# Microcontroller.net
KiCad netlist of a schematic drawn in Altium Designer
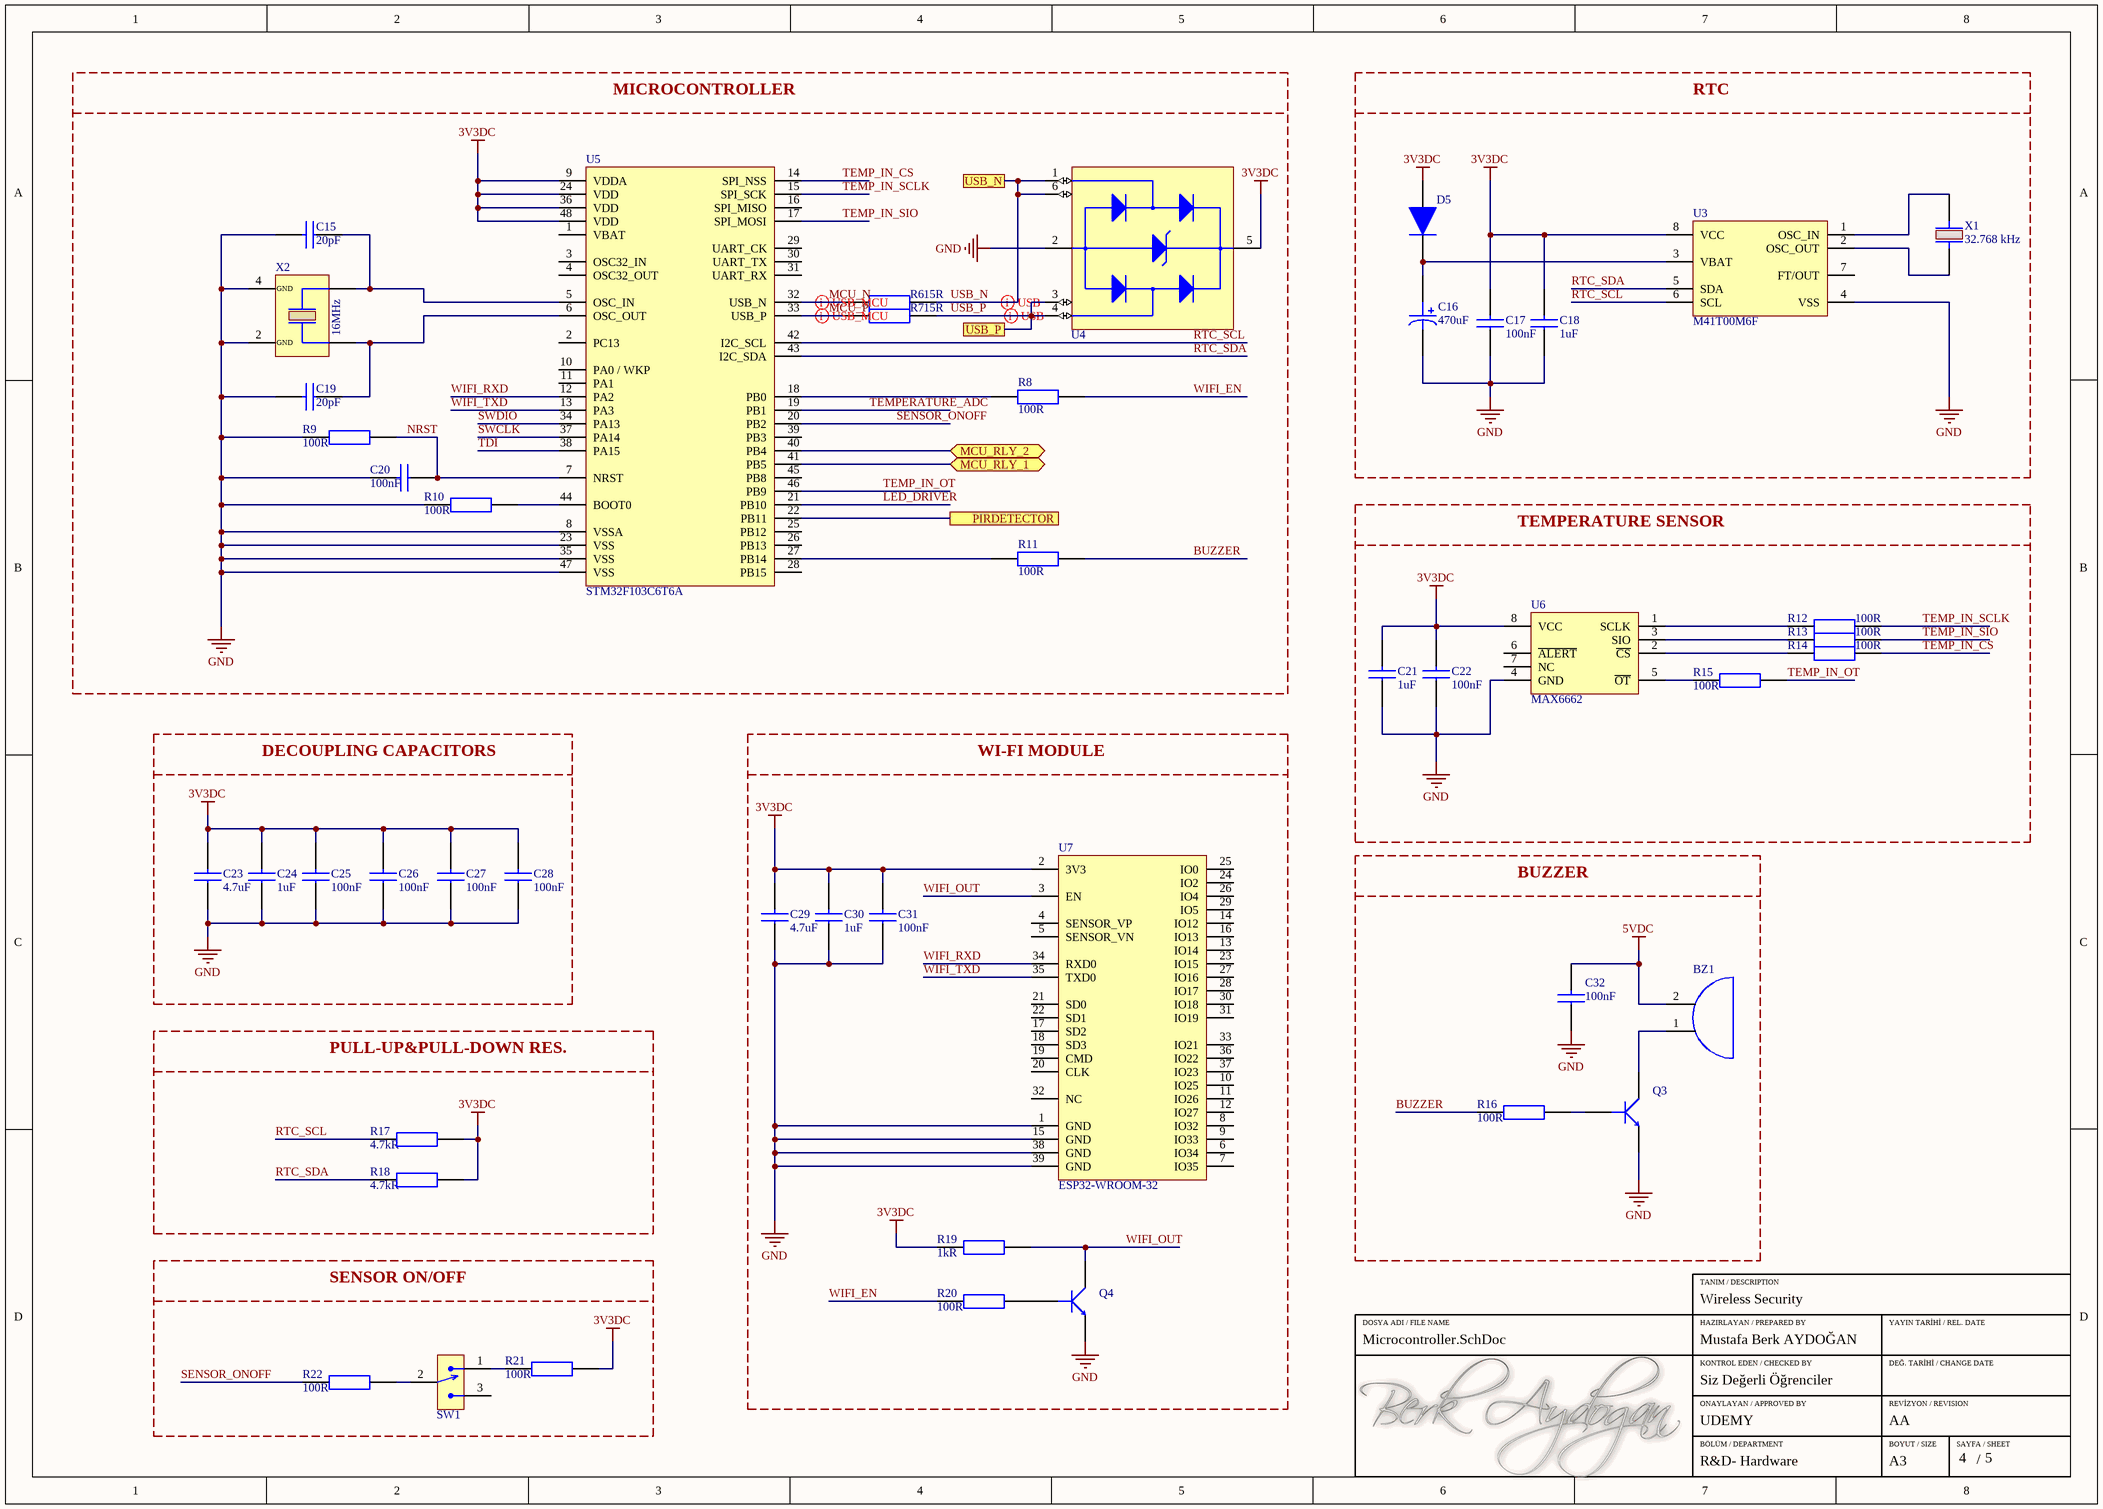
[diagram p0: Microcontroller.SchDoc]

(export (version "E")
  (design (tool "Eeschema 10.0.6"))
  (components
    (comp (ref "BZ1")
      (value "CMI-9605IC-0580T")
      (footprint "CMI-9605IC")
      (description "Buzzers Indicator, Internally Driven Magnetic 5V 30mA 2.7kHz 80dB @ 5V, 10cm Through Hole PC Pins")
      (fields (field (name "MANUFACTURER") "CUI Devices") (field (name "DESIGNED BY") "BERK"))
      (libsource (lib "UDEMY_Library") (part "CMI-9605IC-0580T"))
    )
    (comp (ref "C15")
      (value "CL10C200JB8NNNC")
      (footprint "CAP_0603")
      (description "CAP CER 20pF %5 0603 SMD")
      (fields
        (field (name "MANUFACTURER") "Samsung")
        (field (name "TOLERANCE") "5%")
        (field (name "CAPACITANCE") "20pF")
        (field (name "DESIGNED BY") "BERK")
      )
      (libsource (lib "UDEMY_Library") (part "CAP CER 20pF 0603"))
    )
    (comp (ref "C16")
      (value "ESH477M050AH4AA")
      (footprint "CAP_RADIAL_D10_P5")
      (description "CAP ALU ELEC 470uF 50V RADIAL")
      (fields
        (field (name "MANUFACTURER") "KEMET")
        (field (name "TOLERANCE") "20%")
        (field (name "CAPACITANCE") "470uF")
        (field (name "DESIGNED BY") "BERK")
      )
      (libsource (lib "UDEMY_Library") (part "CAP ALU ELEC 470uF 50V"))
    )
    (comp (ref "C17")
      (value "CL21B104KBCNNNC")
      (footprint "CAP_0805")
      (description "CAP CER 100nF %10 0805")
      (fields
        (field (name "MANUFACTURER") "Samsung")
        (field (name "TOLERANCE") "10%")
        (field (name "CAPACITANCE") "100nF")
        (field (name "DESIGNED BY") "BERK")
      )
      (libsource (lib "UDEMY_Library") (part "CAP CER 100nF 0805"))
    )
    (comp (ref "C18")
      (value "CL21B105KBFNNNE")
      (footprint "CAP_0805")
      (description "CAP CER 1uF %10 0805")
      (fields
        (field (name "MANUFACTURER") "Samsung")
        (field (name "TOLERANCE") "10%")
        (field (name "CAPACITANCE") "1uF")
        (field (name "DESIGNED BY") "BERK")
      )
      (libsource (lib "UDEMY_Library") (part "CAP CER 1uF 0805"))
    )
    (comp (ref "C19")
      (value "CL10C200JB8NNNC")
      (footprint "CAP_0603")
      (description "CAP CER 20pF %5 0603 SMD")
      (fields
        (field (name "MANUFACTURER") "Samsung")
        (field (name "TOLERANCE") "5%")
        (field (name "CAPACITANCE") "20pF")
        (field (name "DESIGNED BY") "BERK")
      )
      (libsource (lib "UDEMY_Library") (part "CAP CER 20pF 0603"))
    )
    (comp (ref "C20")
      (value "C0603C104K5RACTU")
      (footprint "CAP_0603")
      (description "CAP CER 100nF %10 0603 SMD")
      (fields
        (field (name "MANUFACTURER") "KEMET")
        (field (name "TOLERANCE") "10%")
        (field (name "CAPACITANCE") "100nF")
        (field (name "DESIGNED BY") "BERK")
      )
      (libsource (lib "UDEMY_Library") (part "CAP CER 100nF 0603"))
    )
    (comp (ref "C21")
      (value "CL21B105KBFNNNE")
      (footprint "CAP_0805")
      (description "CAP CER 1uF %10 0805")
      (fields
        (field (name "MANUFACTURER") "Samsung")
        (field (name "TOLERANCE") "10%")
        (field (name "CAPACITANCE") "1uF")
        (field (name "DESIGNED BY") "BERK")
      )
      (libsource (lib "UDEMY_Library") (part "CAP CER 1uF 0805"))
    )
    (comp (ref "C22")
      (value "CL21B104KBCNNNC")
      (footprint "CAP_0805")
      (description "CAP CER 100nF %10 0805")
      (fields
        (field (name "MANUFACTURER") "Samsung")
        (field (name "TOLERANCE") "10%")
        (field (name "CAPACITANCE") "100nF")
        (field (name "DESIGNED BY") "BERK")
      )
      (libsource (lib "UDEMY_Library") (part "CAP CER 100nF 0805"))
    )
    (comp (ref "C23")
      (value "CL21A475KAQNNNE")
      (footprint "CAP_0805")
      (description "CAP CER 4.7uF %10 0805")
      (fields
        (field (name "MANUFACTURER") "Samsung")
        (field (name "TOLERANCE") "10%")
        (field (name "CAPACITANCE") "4.7uF")
        (field (name "DESIGNED BY") "BERK")
      )
      (libsource (lib "UDEMY_Library") (part "CAP CER 4.7uF 0805"))
    )
    (comp (ref "C24")
      (value "CL21B105KBFNNNE")
      (footprint "CAP_0805")
      (description "CAP CER 1uF %10 0805")
      (fields
        (field (name "MANUFACTURER") "Samsung")
        (field (name "TOLERANCE") "10%")
        (field (name "CAPACITANCE") "1uF")
        (field (name "DESIGNED BY") "BERK")
      )
      (libsource (lib "UDEMY_Library") (part "CAP CER 1uF 0805"))
    )
    (comp (ref "C25")
      (value "C0603C104K5RACTU")
      (footprint "CAP_0603")
      (description "CAP CER 100nF %10 0603 SMD")
      (fields
        (field (name "MANUFACTURER") "KEMET")
        (field (name "TOLERANCE") "10%")
        (field (name "CAPACITANCE") "100nF")
        (field (name "DESIGNED BY") "BERK")
      )
      (libsource (lib "UDEMY_Library") (part "CAP CER 100nF 0603"))
    )
    (comp (ref "C26")
      (value "C0603C104K5RACTU")
      (footprint "CAP_0603")
      (description "CAP CER 100nF %10 0603 SMD")
      (fields
        (field (name "MANUFACTURER") "KEMET")
        (field (name "TOLERANCE") "10%")
        (field (name "CAPACITANCE") "100nF")
        (field (name "DESIGNED BY") "BERK")
      )
      (libsource (lib "UDEMY_Library") (part "CAP CER 100nF 0603"))
    )
    (comp (ref "C27")
      (value "C0603C104K5RACTU")
      (footprint "CAP_0603")
      (description "CAP CER 100nF %10 0603 SMD")
      (fields
        (field (name "MANUFACTURER") "KEMET")
        (field (name "TOLERANCE") "10%")
        (field (name "CAPACITANCE") "100nF")
        (field (name "DESIGNED BY") "BERK")
      )
      (libsource (lib "UDEMY_Library") (part "CAP CER 100nF 0603"))
    )
    (comp (ref "C28")
      (value "C0603C104K5RACTU")
      (footprint "CAP_0603")
      (description "CAP CER 100nF %10 0603 SMD")
      (fields
        (field (name "MANUFACTURER") "KEMET")
        (field (name "TOLERANCE") "10%")
        (field (name "CAPACITANCE") "100nF")
        (field (name "DESIGNED BY") "BERK")
      )
      (libsource (lib "UDEMY_Library") (part "CAP CER 100nF 0603"))
    )
    (comp (ref "C29")
      (value "CL21A475KAQNNNE")
      (footprint "CAP_0805")
      (description "CAP CER 4.7uF %10 0805")
      (fields
        (field (name "MANUFACTURER") "Samsung")
        (field (name "TOLERANCE") "10%")
        (field (name "CAPACITANCE") "4.7uF")
        (field (name "DESIGNED BY") "BERK")
      )
      (libsource (lib "UDEMY_Library") (part "CAP CER 4.7uF 0805"))
    )
    (comp (ref "C30")
      (value "CL21B105KBFNNNE")
      (footprint "CAP_0805")
      (description "CAP CER 1uF %10 0805")
      (fields
        (field (name "MANUFACTURER") "Samsung")
        (field (name "TOLERANCE") "10%")
        (field (name "CAPACITANCE") "1uF")
        (field (name "DESIGNED BY") "BERK")
      )
      (libsource (lib "UDEMY_Library") (part "CAP CER 1uF 0805"))
    )
    (comp (ref "C31")
      (value "CL21B104KBCNNNC")
      (footprint "CAP_0805")
      (description "CAP CER 100nF %10 0805")
      (fields
        (field (name "MANUFACTURER") "Samsung")
        (field (name "TOLERANCE") "10%")
        (field (name "CAPACITANCE") "100nF")
        (field (name "DESIGNED BY") "BERK")
      )
      (libsource (lib "UDEMY_Library") (part "CAP CER 100nF 0805"))
    )
    (comp (ref "C32")
      (value "CL21B104KBCNNNC")
      (footprint "CAP_0805")
      (description "CAP CER 100nF %10 0805")
      (fields
        (field (name "MANUFACTURER") "Samsung")
        (field (name "TOLERANCE") "10%")
        (field (name "CAPACITANCE") "100nF")
        (field (name "DESIGNED BY") "BERK")
      )
      (libsource (lib "UDEMY_Library") (part "CAP CER 100nF 0805"))
    )
    (comp (ref "D5")
      (value "1N4148WS")
      (footprint "SOD323F")
      (description "Diode, Single, 75 V, 150 mA, 1 V, 4 ns")
      (fields
        (field (name "MANUFACTURER") "ON Semiconductor / Fairchild")
        (field (name "DESIGNED BY") "BERK")
      )
      (libsource (lib "UDEMY_Library") (part "1N4148WS"))
    )
    (comp (ref "Q3")
      (value "MMBT3904-7-F")
      (footprint "SOT-23F")
      (description "Transistor General Purpose BJT NPN 40 Volt 0.2A Automotive 3-Pin SOT-23")
      (fields (field (name "MANUFACTURER") "Diodes Zetex") (field (name "DESIGNED BY") "BERK"))
      (libsource (lib "UDEMY_Library") (part "MMBT3904-7-F"))
    )
    (comp (ref "Q4")
      (value "MMBT3904-7-F")
      (footprint "SOT-23F")
      (description "Transistor General Purpose BJT NPN 40 Volt 0.2A Automotive 3-Pin SOT-23")
      (fields (field (name "MANUFACTURER") "Diodes Zetex") (field (name "DESIGNED BY") "BERK"))
      (libsource (lib "UDEMY_Library") (part "MMBT3904-7-F"))
    )
    (comp (ref "R6")
      (value "RC0603JR-0715RL")
      (footprint "RES_0603")
      (description "RES 15 %5 OHM 0603 SMD")
      (fields
        (field (name "MANUFACTURER") "Yageo")
        (field (name "TOLERANCE") "5%")
        (field (name "RESISTANCE") "15R")
        (field (name "DESIGNED BY") "BERK")
      )
      (libsource (lib "UDEMY_Library") (part "RES 15 OHM 0603"))
    )
    (comp (ref "R7")
      (value "RC0603JR-0715RL")
      (footprint "RES_0603")
      (description "RES 15 %5 OHM 0603 SMD")
      (fields
        (field (name "MANUFACTURER") "Yageo")
        (field (name "TOLERANCE") "5%")
        (field (name "RESISTANCE") "15R")
        (field (name "DESIGNED BY") "BERK")
      )
      (libsource (lib "UDEMY_Library") (part "RES 15 OHM 0603"))
    )
    (comp (ref "R8")
      (value "RC0603JR-07100RL")
      (footprint "RES_0603")
      (description "RES 100 %5 OHM 0603 SMD")
      (fields
        (field (name "MANUFACTURER") "Yageo")
        (field (name "TOLERANCE") "5%")
        (field (name "RESISTANCE") "100R")
        (field (name "DESIGNED BY") "BERK")
      )
      (libsource (lib "") (part "RES 100 OHM 0603_1"))
    )
    (comp (ref "R9")
      (value "RC0603JR-07100RL")
      (footprint "RES_0603")
      (description "RES 100 %5 OHM 0603 SMD")
      (fields
        (field (name "MANUFACTURER") "Yageo")
        (field (name "TOLERANCE") "5%")
        (field (name "RESISTANCE") "100R")
        (field (name "DESIGNED BY") "BERK")
      )
      (libsource (lib "") (part "RES 100 OHM 0603_1"))
    )
    (comp (ref "R10")
      (value "RC0603JR-07100RL")
      (footprint "RES_0603")
      (description "RES 100 %5 OHM 0603 SMD")
      (fields
        (field (name "MANUFACTURER") "Yageo")
        (field (name "TOLERANCE") "5%")
        (field (name "RESISTANCE") "100R")
        (field (name "DESIGNED BY") "BERK")
      )
      (libsource (lib "") (part "RES 100 OHM 0603_1"))
    )
    (comp (ref "R11")
      (value "RC0603JR-07100RL")
      (footprint "RES_0603")
      (description "RES 100 %5 OHM 0603 SMD")
      (fields
        (field (name "MANUFACTURER") "Yageo")
        (field (name "TOLERANCE") "5%")
        (field (name "RESISTANCE") "100R")
        (field (name "DESIGNED BY") "BERK")
      )
      (libsource (lib "") (part "RES 100 OHM 0603_1"))
    )
    (comp (ref "R12")
      (value "RC0603JR-07100RL")
      (footprint "RES_0603")
      (description "RES 100 %5 OHM 0603 SMD")
      (fields
        (field (name "MANUFACTURER") "Yageo")
        (field (name "TOLERANCE") "5%")
        (field (name "RESISTANCE") "100R")
        (field (name "DESIGNED BY") "BERK")
      )
      (libsource (lib "") (part "RES 100 OHM 0603_1"))
    )
    (comp (ref "R13")
      (value "RC0603JR-07100RL")
      (footprint "RES_0603")
      (description "RES 100 %5 OHM 0603 SMD")
      (fields
        (field (name "MANUFACTURER") "Yageo")
        (field (name "TOLERANCE") "5%")
        (field (name "RESISTANCE") "100R")
        (field (name "DESIGNED BY") "BERK")
      )
      (libsource (lib "") (part "RES 100 OHM 0603_1"))
    )
    (comp (ref "R14")
      (value "RC0603JR-07100RL")
      (footprint "RES_0603")
      (description "RES 100 %5 OHM 0603 SMD")
      (fields
        (field (name "MANUFACTURER") "Yageo")
        (field (name "TOLERANCE") "5%")
        (field (name "RESISTANCE") "100R")
        (field (name "DESIGNED BY") "BERK")
      )
      (libsource (lib "") (part "RES 100 OHM 0603_1"))
    )
    (comp (ref "R15")
      (value "RC0603JR-07100RL")
      (footprint "RES_0603")
      (description "RES 100 %5 OHM 0603 SMD")
      (fields
        (field (name "MANUFACTURER") "Yageo")
        (field (name "TOLERANCE") "5%")
        (field (name "RESISTANCE") "100R")
        (field (name "DESIGNED BY") "BERK")
      )
      (libsource (lib "") (part "RES 100 OHM 0603_1"))
    )
    (comp (ref "R16")
      (value "RC0603JR-07100RL")
      (footprint "RES_0603")
      (description "RES 100 %5 OHM 0603 SMD")
      (fields
        (field (name "MANUFACTURER") "Yageo")
        (field (name "TOLERANCE") "5%")
        (field (name "RESISTANCE") "100R")
        (field (name "DESIGNED BY") "BERK")
      )
      (libsource (lib "") (part "RES 100 OHM 0603_1"))
    )
    (comp (ref "R17")
      (value "RC0603JR-074K7L")
      (footprint "RES_0603")
      (description "RES 4K7 %5 OHM 0603 SMD")
      (fields
        (field (name "MANUFACTURER") "Yageo")
        (field (name "TOLERANCE") "5%")
        (field (name "RESISTANCE") "4.7kR")
        (field (name "DESIGNED BY") "BERK")
      )
      (libsource (lib "UDEMY_Library") (part "RES 4K7 OHM 0603"))
    )
    (comp (ref "R18")
      (value "RC0603JR-074K7L")
      (footprint "RES_0603")
      (description "RES 4K7 %5 OHM 0603 SMD")
      (fields
        (field (name "MANUFACTURER") "Yageo")
        (field (name "TOLERANCE") "5%")
        (field (name "RESISTANCE") "4.7kR")
        (field (name "DESIGNED BY") "BERK")
      )
      (libsource (lib "UDEMY_Library") (part "RES 4K7 OHM 0603"))
    )
    (comp (ref "R19")
      (value "RC0603FR-0710KL")
      (footprint "RES_0603")
      (description "RES 1K %1 OHM 0603 SMD")
      (fields
        (field (name "MANUFACTURER") "Yageo")
        (field (name "MANUFACTURER PART NUMBER") "RC0603JR-071KL")
        (field (name "RESISTANCE") "1kR")
        (field (name "DESIGNED BY") "BERK")
      )
      (libsource (lib "UDEMY_Library") (part "RES 1K OHM 0603"))
    )
    (comp (ref "R20")
      (value "RC0603JR-07100RL")
      (footprint "RES_0603")
      (description "RES 100 %5 OHM 0603 SMD")
      (fields
        (field (name "MANUFACTURER") "Yageo")
        (field (name "TOLERANCE") "5%")
        (field (name "RESISTANCE") "100R")
        (field (name "DESIGNED BY") "BERK")
      )
      (libsource (lib "") (part "RES 100 OHM 0603_1"))
    )
    (comp (ref "R21")
      (value "RC0603JR-07100RL")
      (footprint "RES_0603")
      (description "RES 100 %5 OHM 0603 SMD")
      (fields
        (field (name "MANUFACTURER") "Yageo")
        (field (name "TOLERANCE") "5%")
        (field (name "RESISTANCE") "100R")
        (field (name "DESIGNED BY") "BERK")
      )
      (libsource (lib "") (part "RES 100 OHM 0603_1"))
    )
    (comp (ref "R22")
      (value "RC0603JR-07100RL")
      (footprint "RES_0603")
      (description "RES 100 %5 OHM 0603 SMD")
      (fields
        (field (name "MANUFACTURER") "Yageo")
        (field (name "TOLERANCE") "5%")
        (field (name "RESISTANCE") "100R")
        (field (name "DESIGNED BY") "BERK")
      )
      (libsource (lib "UDEMY_Library") (part "RES 100 OHM 0603"))
    )
    (comp (ref "SW1")
      (value "EG1215AA")
      (footprint "EG1215AA")
      (description "Slide Switch, SPDT, 0.025A, 24V, SMD")
      (fields
        (field (name "MANUFACTURER") "E-Switch")
        (field (name "TOLERANCE") "4.95%")
        (field (name "DESIGNED BY") "BERK")
      )
      (libsource (lib "UDEMY_Library") (part "EG1215AA"))
    )
    (comp (ref "U3")
      (value "M41T00M6F")
      (footprint "SOIC8")
      (description "IC RTC CLK/CALENDAR I2C 8-SOIC")
      (fields (field (name "MANUFACTURER") "STMicroelectronics") (field (name "DESIGNED BY") "BERK"))
      (libsource (lib "UDEMY_Library") (part "M41T00M6F"))
    )
    (comp (ref "U4")
      (value "USBLC6-2SC6")
      (footprint "SOT23-6L")
      (description "TVS DIODE 5.25V 17V SOT23-6")
      (fields (field (name "MANUFACTURER") "STMicroelectronics") (field (name "DESIGNED BY") "BERK"))
      (libsource (lib "UDEMY_Library") (part "USB PROTECTION"))
    )
    (comp (ref "U5")
      (value "STM32F103C6T6A")
      (footprint "LQFP-48")
      (description "MCU 32-bit STM32F ARM Cortex M3 RISC 32KB Flash 2.5V/3.3V 48-Pin LQFP Tray")
      (fields (field (name "MANUFACTURER") "STMicroelectronics") (field (name "DESIGNED BY") "BERK"))
      (libsource (lib "UDEMY_Library") (part "STM32F103C6T6A"))
    )
    (comp (ref "U6")
      (value "MAX6662")
      (footprint "SOIC8")
      (description "SENSOR TEMPERATURE SPI 8SOIC")
      (fields
        (field (name "MANUFACTURER") "Maxim")
        (field (name "MANUFACTURER PART NUMBER") "MAX6662MSA+")
        (field (name "DESIGNED BY") "BERK")
      )
      (libsource (lib "UDEMY_Library") (part "MAX6662"))
    )
    (comp (ref "U7")
      (value "ESP32-WROOM-32")
      (footprint "ESP32-32")
      (description "SMD MODULE, ESP32-D0WDQ6, 32MBIT")
      (fields (field (name "MANUFACTURER") "Espressif Systems") (field (name "DESIGNED BY") "BERK"))
      (libsource (lib "UDEMY_Library") (part "ESP32-WROOM-32"))
    )
    (comp (ref "X1")
      (value "ABS05-32.768KHZ-T")
      (footprint "ABS05")
      (description "Crystal, 32.768 kHz, SMD, 1.6mm x 1mm, 12.5 pF, 20 ppm, ABS05 Series")
      (fields
        (field (name "MANUFACTURER") "Abracon")
        (field (name "TOLERANCE") "20ppm")
        (field (name "OPERATING FREQUENCY") "32.768 kHz")
        (field (name "DESIGNED BY") "BERK")
      )
      (libsource (lib "UDEMY_Library") (part "CRYSTAL 32768kHZ"))
    )
    (comp (ref "X2")
      (value "ECS-160-20-30B-TR")
      (footprint "ECS")
      (description "CRYSTAL 16.0000MHZ 20PF SMD")
      (fields
        (field (name "MANUFACTURER") "ECS International")
        (field (name "TOLERANCE") "50ppm")
        (field (name "FREQUENCY") "16MHz")
        (field (name "DESIGNED BY") "BERK")
      )
      (libsource (lib "UDEMY_Library") (part "CRYSTAL 16MHz"))
    )
  )
  (nets
    (net (code "1") (name "/BUZZER") (class "Default")
      (node (ref "R11") (pin "2") (pinfunction "2_2") (pintype "passive"))
      (node (ref "R16") (pin "1") (pinfunction "1_1") (pintype "passive"))
    )
    (net (code "2") (name "/LED_DRIVER") (class "Default")
      (node (ref "U5") (pin "21") (pinfunction "PB10_21") (pintype "passive"))
    )
    (net (code "3") (name "/MCU_N") (class "Default")
      (node (ref "R6") (pin "1") (pinfunction "1_1") (pintype "passive"))
      (node (ref "U5") (pin "32") (pinfunction "USB_N_32") (pintype "passive"))
    )
    (net (code "4") (name "/MCU_P") (class "Default")
      (node (ref "R7") (pin "1") (pinfunction "1_1") (pintype "passive"))
      (node (ref "U5") (pin "33") (pinfunction "USB_P_33") (pintype "passive"))
    )
    (net (code "5") (name "/MCU_RLY_1") (class "Default")
      (node (ref "U5") (pin "41") (pinfunction "PB5_41") (pintype "passive"))
    )
    (net (code "6") (name "/MCU_RLY_2") (class "Default")
      (node (ref "U5") (pin "40") (pinfunction "PB4_40") (pintype "passive"))
    )
    (net (code "7") (name "/NRST") (class "Default")
      (node (ref "C20") (pin "1") (pinfunction "1_1") (pintype "passive"))
      (node (ref "R9") (pin "2") (pinfunction "2_2") (pintype "passive"))
      (node (ref "U5") (pin "7") (pinfunction "NRST_7") (pintype "passive"))
    )
    (net (code "8") (name "/PIRDETECTOR") (class "Default")
      (node (ref "U5") (pin "22") (pinfunction "PB11_22") (pintype "passive"))
    )
    (net (code "9") (name "/RTC_SCL") (class "Default")
      (node (ref "R17") (pin "1") (pinfunction "1_1") (pintype "passive"))
      (node (ref "U3") (pin "6") (pinfunction "SCL_6") (pintype "passive"))
      (node (ref "U5") (pin "42") (pinfunction "I2C_SCL_42") (pintype "passive"))
    )
    (net (code "10") (name "/RTC_SDA") (class "Default")
      (node (ref "R18") (pin "1") (pinfunction "1_1") (pintype "passive"))
      (node (ref "U3") (pin "5") (pinfunction "SDA_5") (pintype "passive"))
      (node (ref "U5") (pin "43") (pinfunction "I2C_SDA_43") (pintype "passive"))
    )
    (net (code "11") (name "/SENSOR_ONOFF") (class "Default")
      (node (ref "R22") (pin "2") (pinfunction "2_2") (pintype "passive"))
      (node (ref "U5") (pin "20") (pinfunction "PB2_20") (pintype "passive"))
    )
    (net (code "12") (name "/SWCLK") (class "Default")
      (node (ref "U5") (pin "37") (pinfunction "PA14_37") (pintype "passive"))
    )
    (net (code "13") (name "/SWDIO") (class "Default")
      (node (ref "U5") (pin "34") (pinfunction "PA13_34") (pintype "passive"))
    )
    (net (code "14") (name "/TDI") (class "Default")
      (node (ref "U5") (pin "38") (pinfunction "PA15_38") (pintype "passive"))
    )
    (net (code "15") (name "/TEMPERATURE_ADC") (class "Default")
      (node (ref "U5") (pin "19") (pinfunction "PB1_19") (pintype "passive"))
    )
    (net (code "16") (name "/TEMP_IN_CS") (class "Default")
      (node (ref "R14") (pin "2") (pinfunction "2_2") (pintype "passive"))
      (node (ref "U5") (pin "14") (pinfunction "SPI_NSS_14") (pintype "passive"))
    )
    (net (code "17") (name "/TEMP_IN_OT") (class "Default")
      (node (ref "R15") (pin "2") (pinfunction "2_2") (pintype "passive"))
      (node (ref "U5") (pin "46") (pinfunction "PB9_46") (pintype "passive"))
    )
    (net (code "18") (name "/TEMP_IN_SCLK") (class "Default")
      (node (ref "R12") (pin "2") (pinfunction "2_2") (pintype "passive"))
      (node (ref "U5") (pin "15") (pinfunction "SPI_SCK_15") (pintype "passive"))
    )
    (net (code "19") (name "/TEMP_IN_SIO") (class "Default")
      (node (ref "R13") (pin "2") (pinfunction "2_2") (pintype "passive"))
      (node (ref "U5") (pin "17") (pinfunction "SPI_MOSI_17") (pintype "passive"))
    )
    (net (code "20") (name "/USB_N") (class "Default")
      (node (ref "R6") (pin "2") (pinfunction "2_2") (pintype "passive"))
      (node (ref "U4") (pin "1") (pinfunction "I/O1_1") (pintype "bidirectional"))
      (node (ref "U4") (pin "6") (pinfunction "I/O1_6") (pintype "bidirectional"))
    )
    (net (code "21") (name "/USB_P") (class "Default")
      (node (ref "R7") (pin "2") (pinfunction "2_2") (pintype "passive"))
      (node (ref "U4") (pin "3") (pinfunction "I/O2_3") (pintype "bidirectional"))
      (node (ref "U4") (pin "4") (pinfunction "I/O2_4") (pintype "bidirectional"))
    )
    (net (code "22") (name "/WIFI_EN") (class "Default")
      (node (ref "R20") (pin "1") (pinfunction "1_1") (pintype "passive"))
      (node (ref "R8") (pin "2") (pinfunction "2_2") (pintype "passive"))
    )
    (net (code "23") (name "/WIFI_OUT") (class "Default")
      (node (ref "Q4") (pin "3") (pinfunction "C_3") (pintype "power_in"))
      (node (ref "R19") (pin "1") (pinfunction "1_1") (pintype "passive"))
      (node (ref "U7") (pin "3") (pinfunction "EN_3") (pintype "passive"))
    )
    (net (code "24") (name "/WIFI_RXD") (class "Default")
      (node (ref "U5") (pin "12") (pinfunction "PA2_12") (pintype "passive"))
      (node (ref "U7") (pin "34") (pinfunction "RXD0_34") (pintype "passive"))
    )
    (net (code "25") (name "/WIFI_TXD") (class "Default")
      (node (ref "U5") (pin "13") (pinfunction "PA3_13") (pintype "passive"))
      (node (ref "U7") (pin "35") (pinfunction "TXD0_35") (pintype "passive"))
    )
    (net (code "26") (name "3V3DC") (class "Default")
      (node (ref "C17") (pin "2") (pinfunction "2_2") (pintype "passive"))
      (node (ref "C18") (pin "2") (pinfunction "2_2") (pintype "passive"))
      (node (ref "C21") (pin "2") (pinfunction "2_2") (pintype "passive"))
      (node (ref "C22") (pin "2") (pinfunction "2_2") (pintype "passive"))
      (node (ref "C23") (pin "2") (pinfunction "2_2") (pintype "passive"))
      (node (ref "C24") (pin "2") (pinfunction "2_2") (pintype "passive"))
      (node (ref "C25") (pin "2") (pinfunction "2_2") (pintype "passive"))
      (node (ref "C26") (pin "2") (pinfunction "2_2") (pintype "passive"))
      (node (ref "C27") (pin "2") (pinfunction "2_2") (pintype "passive"))
      (node (ref "C28") (pin "2") (pinfunction "2_2") (pintype "passive"))
      (node (ref "C29") (pin "2") (pinfunction "2_2") (pintype "passive"))
      (node (ref "C30") (pin "2") (pinfunction "2_2") (pintype "passive"))
      (node (ref "C31") (pin "2") (pinfunction "2_2") (pintype "passive"))
      (node (ref "D5") (pin "2") (pinfunction "2_2") (pintype "power_in"))
      (node (ref "R17") (pin "2") (pinfunction "2_2") (pintype "passive"))
      (node (ref "R18") (pin "2") (pinfunction "2_2") (pintype "passive"))
      (node (ref "R19") (pin "2") (pinfunction "2_2") (pintype "passive"))
      (node (ref "R21") (pin "2") (pinfunction "2_2") (pintype "passive"))
      (node (ref "U3") (pin "8") (pinfunction "VCC_8") (pintype "passive"))
      (node (ref "U4") (pin "5") (pinfunction "VBUS_5") (pintype "power_in"))
      (node (ref "U5") (pin "24") (pinfunction "VDD_24") (pintype "passive"))
      (node (ref "U5") (pin "36") (pinfunction "VDD_36") (pintype "passive"))
      (node (ref "U5") (pin "48") (pinfunction "VDD_48") (pintype "passive"))
      (node (ref "U5") (pin "9") (pinfunction "VDDA_9") (pintype "passive"))
      (node (ref "U6") (pin "8") (pinfunction "VCC_8") (pintype "passive"))
      (node (ref "U7") (pin "2") (pinfunction "3V3_2") (pintype "passive"))
    )
    (net (code "27") (name "5VDC") (class "Default")
      (node (ref "BZ1") (pin "2") (pinfunction "2_2") (pintype "passive"))
      (node (ref "C32") (pin "2") (pinfunction "2_2") (pintype "passive"))
    )
    (net (code "28") (name "GND") (class "Default")
      (node (ref "C15") (pin "2") (pinfunction "2_2") (pintype "passive"))
      (node (ref "C16") (pin "2") (pinfunction "2_2") (pintype "passive"))
      (node (ref "C17") (pin "1") (pinfunction "1_1") (pintype "passive"))
      (node (ref "C18") (pin "1") (pinfunction "1_1") (pintype "passive"))
      (node (ref "C19") (pin "2") (pinfunction "2_2") (pintype "passive"))
      (node (ref "C20") (pin "2") (pinfunction "2_2") (pintype "passive"))
      (node (ref "C21") (pin "1") (pinfunction "1_1") (pintype "passive"))
      (node (ref "C22") (pin "1") (pinfunction "1_1") (pintype "passive"))
      (node (ref "C23") (pin "1") (pinfunction "1_1") (pintype "passive"))
      (node (ref "C24") (pin "1") (pinfunction "1_1") (pintype "passive"))
      (node (ref "C25") (pin "1") (pinfunction "1_1") (pintype "passive"))
      (node (ref "C26") (pin "1") (pinfunction "1_1") (pintype "passive"))
      (node (ref "C27") (pin "1") (pinfunction "1_1") (pintype "passive"))
      (node (ref "C28") (pin "1") (pinfunction "1_1") (pintype "passive"))
      (node (ref "C29") (pin "1") (pinfunction "1_1") (pintype "passive"))
      (node (ref "C30") (pin "1") (pinfunction "1_1") (pintype "passive"))
      (node (ref "C31") (pin "1") (pinfunction "1_1") (pintype "passive"))
      (node (ref "C32") (pin "1") (pinfunction "1_1") (pintype "passive"))
      (node (ref "Q3") (pin "2") (pinfunction "E_2") (pintype "power_in"))
      (node (ref "Q4") (pin "2") (pinfunction "E_2") (pintype "power_in"))
      (node (ref "R10") (pin "1") (pinfunction "1_1") (pintype "passive"))
      (node (ref "R9") (pin "1") (pinfunction "1_1") (pintype "passive"))
      (node (ref "U3") (pin "4") (pinfunction "VSS_4") (pintype "passive"))
      (node (ref "U4") (pin "2") (pinfunction "GND_2") (pintype "power_in"))
      (node (ref "U5") (pin "23") (pinfunction "VSS_23") (pintype "passive"))
      (node (ref "U5") (pin "35") (pinfunction "VSS_35") (pintype "passive"))
      (node (ref "U5") (pin "47") (pinfunction "VSS_47") (pintype "passive"))
      (node (ref "U5") (pin "8") (pinfunction "VSSA_8") (pintype "passive"))
      (node (ref "U6") (pin "4") (pinfunction "GND_4") (pintype "passive"))
      (node (ref "U7") (pin "1") (pinfunction "GND_1") (pintype "passive"))
      (node (ref "U7") (pin "15") (pinfunction "GND_15") (pintype "passive"))
      (node (ref "U7") (pin "38") (pinfunction "GND_38") (pintype "passive"))
      (node (ref "U7") (pin "39") (pinfunction "GND_39") (pintype "passive"))
      (node (ref "X2") (pin "2") (pinfunction "GND_2") (pintype "passive"))
      (node (ref "X2") (pin "4") (pinfunction "GND_4") (pintype "passive"))
    )
    (net (code "29") (name "Net-(Q3-B)") (class "Default")
      (node (ref "Q3") (pin "1") (pinfunction "B_1") (pintype "power_in"))
      (node (ref "R16") (pin "2") (pinfunction "2_2") (pintype "passive"))
    )
    (net (code "30") (name "Net-(Q3-C)") (class "Default")
      (node (ref "BZ1") (pin "1") (pinfunction "1_1") (pintype "passive"))
      (node (ref "Q3") (pin "3") (pinfunction "C_3") (pintype "power_in"))
    )
    (net (code "31") (name "Net-(Q4-B)") (class "Default")
      (node (ref "Q4") (pin "1") (pinfunction "B_1") (pintype "power_in"))
      (node (ref "R20") (pin "2") (pinfunction "2_2") (pintype "passive"))
    )
    (net (code "32") (name "Net-(R21-Pad1)") (class "Default")
      (node (ref "R21") (pin "1") (pinfunction "1_1") (pintype "passive"))
      (node (ref "SW1") (pin "1") (pinfunction "1_1") (pintype "passive"))
    )
    (net (code "33") (name "Net-(R22-Pad1)") (class "Default")
      (node (ref "R22") (pin "1") (pinfunction "1_1") (pintype "passive"))
      (node (ref "SW1") (pin "2") (pinfunction "2_2") (pintype "passive"))
    )
    (net (code "34") (name "Net-(U3-OSC_IN)") (class "Default")
      (node (ref "U3") (pin "1") (pinfunction "OSC_IN_1") (pintype "passive"))
      (node (ref "X1") (pin "2") (pinfunction "2_2") (pintype "passive"))
    )
    (net (code "35") (name "Net-(U3-OSC_OUT)") (class "Default")
      (node (ref "U3") (pin "2") (pinfunction "OSC_OUT_2") (pintype "passive"))
      (node (ref "X1") (pin "1") (pinfunction "1_1") (pintype "passive"))
    )
    (net (code "36") (name "Net-(U3-VBAT)") (class "Default")
      (node (ref "C16") (pin "1") (pinfunction "1_1") (pintype "passive"))
      (node (ref "D5") (pin "1") (pinfunction "1_1") (pintype "power_in"))
      (node (ref "U3") (pin "3") (pinfunction "VBAT_3") (pintype "passive"))
    )
    (net (code "37") (name "Net-(U5-BOOT0)") (class "Default")
      (node (ref "R10") (pin "2") (pinfunction "2_2") (pintype "passive"))
      (node (ref "U5") (pin "44") (pinfunction "BOOT0_44") (pintype "passive"))
    )
    (net (code "38") (name "Net-(U5-OSC_IN)") (class "Default")
      (node (ref "C15") (pin "1") (pinfunction "1_1") (pintype "passive"))
      (node (ref "U5") (pin "5") (pinfunction "OSC_IN_5") (pintype "passive"))
      (node (ref "X2") (pin "3") (pinfunction "3_3") (pintype "passive"))
    )
    (net (code "39") (name "Net-(U5-OSC_OUT)") (class "Default")
      (node (ref "C19") (pin "1") (pinfunction "1_1") (pintype "passive"))
      (node (ref "U5") (pin "6") (pinfunction "OSC_OUT_6") (pintype "passive"))
      (node (ref "X2") (pin "1") (pinfunction "1_1") (pintype "passive"))
    )
    (net (code "40") (name "Net-(U5-PB0)") (class "Default")
      (node (ref "R8") (pin "1") (pinfunction "1_1") (pintype "passive"))
      (node (ref "U5") (pin "18") (pinfunction "PB0_18") (pintype "passive"))
    )
    (net (code "41") (name "Net-(U5-PB14)") (class "Default")
      (node (ref "R11") (pin "1") (pinfunction "1_1") (pintype "passive"))
      (node (ref "U5") (pin "27") (pinfunction "PB14_27") (pintype "passive"))
    )
    (net (code "42") (name "Net-(U6-SCLK)") (class "Default")
      (node (ref "R12") (pin "1") (pinfunction "1_1") (pintype "passive"))
      (node (ref "U6") (pin "1") (pinfunction "SCLK_1") (pintype "passive"))
    )
    (net (code "43") (name "Net-(U6-SIO)") (class "Default")
      (node (ref "R13") (pin "1") (pinfunction "1_1") (pintype "passive"))
      (node (ref "U6") (pin "3") (pinfunction "SIO_3") (pintype "passive"))
    )
    (net (code "44") (name "Net-(U6-~{CS})") (class "Default")
      (node (ref "R14") (pin "1") (pinfunction "1_1") (pintype "passive"))
      (node (ref "U6") (pin "2") (pinfunction "~{CS}_2") (pintype "passive"))
    )
    (net (code "45") (name "Net-(U6-~{OT})") (class "Default")
      (node (ref "R15") (pin "1") (pinfunction "1_1") (pintype "passive"))
      (node (ref "U6") (pin "5") (pinfunction "~{OT}_5") (pintype "passive"))
    )
    (net (code "46") (name "unconnected-(SW1-Pad3)") (class "Default")
      (node (ref "SW1") (pin "3") (pinfunction "3_3") (pintype "passive"))
    )
    (net (code "47") (name "unconnected-(U3-FT{slash}OUT-Pad7)") (class "Default")
      (node (ref "U3") (pin "7") (pinfunction "FT/OUT_7") (pintype "passive"))
    )
    (net (code "48") (name "unconnected-(U5-OSC32_IN-Pad3)") (class "Default")
      (node (ref "U5") (pin "3") (pinfunction "OSC32_IN_3") (pintype "passive"))
    )
    (net (code "49") (name "unconnected-(U5-OSC32_OUT-Pad4)") (class "Default")
      (node (ref "U5") (pin "4") (pinfunction "OSC32_OUT_4") (pintype "passive"))
    )
    (net (code "50") (name "unconnected-(U5-PA0_{slash}_WKP-Pad10)") (class "Default")
      (node (ref "U5") (pin "10") (pinfunction "PA0_/_WKP_10") (pintype "passive"))
    )
    (net (code "51") (name "unconnected-(U5-PA1-Pad11)") (class "Default")
      (node (ref "U5") (pin "11") (pinfunction "PA1_11") (pintype "passive"))
    )
    (net (code "52") (name "unconnected-(U5-PB3-Pad39)") (class "Default")
      (node (ref "U5") (pin "39") (pinfunction "PB3_39") (pintype "passive"))
    )
    (net (code "53") (name "unconnected-(U5-PB8-Pad45)") (class "Default")
      (node (ref "U5") (pin "45") (pinfunction "PB8_45") (pintype "passive"))
    )
    (net (code "54") (name "unconnected-(U5-PB12-Pad25)") (class "Default")
      (node (ref "U5") (pin "25") (pinfunction "PB12_25") (pintype "passive"))
    )
    (net (code "55") (name "unconnected-(U5-PB13-Pad26)") (class "Default")
      (node (ref "U5") (pin "26") (pinfunction "PB13_26") (pintype "passive"))
    )
    (net (code "56") (name "unconnected-(U5-PB15-Pad28)") (class "Default")
      (node (ref "U5") (pin "28") (pinfunction "PB15_28") (pintype "passive"))
    )
    (net (code "57") (name "unconnected-(U5-PC13-Pad2)") (class "Default")
      (node (ref "U5") (pin "2") (pinfunction "PC13_2") (pintype "passive"))
    )
    (net (code "58") (name "unconnected-(U5-SPI_MISO-Pad16)") (class "Default")
      (node (ref "U5") (pin "16") (pinfunction "SPI_MISO_16") (pintype "passive"))
    )
    (net (code "59") (name "unconnected-(U5-UART_CK-Pad29)") (class "Default")
      (node (ref "U5") (pin "29") (pinfunction "UART_CK_29") (pintype "passive"))
    )
    (net (code "60") (name "unconnected-(U5-UART_RX-Pad31)") (class "Default")
      (node (ref "U5") (pin "31") (pinfunction "UART_RX_31") (pintype "passive"))
    )
    (net (code "61") (name "unconnected-(U5-UART_TX-Pad30)") (class "Default")
      (node (ref "U5") (pin "30") (pinfunction "UART_TX_30") (pintype "passive"))
    )
    (net (code "62") (name "unconnected-(U5-VBAT-Pad1)") (class "Default")
      (node (ref "U5") (pin "1") (pinfunction "VBAT_1") (pintype "passive"))
    )
    (net (code "63") (name "unconnected-(U6-NC-Pad7)") (class "Default")
      (node (ref "U6") (pin "7") (pinfunction "NC_7") (pintype "passive"))
    )
    (net (code "64") (name "unconnected-(U6-~{ALERT}-Pad6)") (class "Default")
      (node (ref "U6") (pin "6") (pinfunction "~{ALERT}_6") (pintype "passive"))
    )
    (net (code "65") (name "unconnected-(U7-CLK-Pad20)") (class "Default")
      (node (ref "U7") (pin "20") (pinfunction "CLK_20") (pintype "passive"))
    )
    (net (code "66") (name "unconnected-(U7-CMD-Pad19)") (class "Default")
      (node (ref "U7") (pin "19") (pinfunction "CMD_19") (pintype "passive"))
    )
    (net (code "67") (name "unconnected-(U7-IO0-Pad25)") (class "Default")
      (node (ref "U7") (pin "25") (pinfunction "IO0_25") (pintype "passive"))
    )
    (net (code "68") (name "unconnected-(U7-IO2-Pad24)") (class "Default")
      (node (ref "U7") (pin "24") (pinfunction "IO2_24") (pintype "passive"))
    )
    (net (code "69") (name "unconnected-(U7-IO4-Pad26)") (class "Default")
      (node (ref "U7") (pin "26") (pinfunction "IO4_26") (pintype "passive"))
    )
    (net (code "70") (name "unconnected-(U7-IO5-Pad29)") (class "Default")
      (node (ref "U7") (pin "29") (pinfunction "IO5_29") (pintype "passive"))
    )
    (net (code "71") (name "unconnected-(U7-IO12-Pad14)") (class "Default")
      (node (ref "U7") (pin "14") (pinfunction "IO12_14") (pintype "passive"))
    )
    (net (code "72") (name "unconnected-(U7-IO13-Pad16)") (class "Default")
      (node (ref "U7") (pin "16") (pinfunction "IO13_16") (pintype "passive"))
    )
    (net (code "73") (name "unconnected-(U7-IO14-Pad13)") (class "Default")
      (node (ref "U7") (pin "13") (pinfunction "IO14_13") (pintype "passive"))
    )
    (net (code "74") (name "unconnected-(U7-IO15-Pad23)") (class "Default")
      (node (ref "U7") (pin "23") (pinfunction "IO15_23") (pintype "passive"))
    )
    (net (code "75") (name "unconnected-(U7-IO16-Pad27)") (class "Default")
      (node (ref "U7") (pin "27") (pinfunction "IO16_27") (pintype "passive"))
    )
    (net (code "76") (name "unconnected-(U7-IO17-Pad28)") (class "Default")
      (node (ref "U7") (pin "28") (pinfunction "IO17_28") (pintype "passive"))
    )
    (net (code "77") (name "unconnected-(U7-IO18-Pad30)") (class "Default")
      (node (ref "U7") (pin "30") (pinfunction "IO18_30") (pintype "passive"))
    )
    (net (code "78") (name "unconnected-(U7-IO19-Pad31)") (class "Default")
      (node (ref "U7") (pin "31") (pinfunction "IO19_31") (pintype "passive"))
    )
    (net (code "79") (name "unconnected-(U7-IO21-Pad33)") (class "Default")
      (node (ref "U7") (pin "33") (pinfunction "IO21_33") (pintype "passive"))
    )
    (net (code "80") (name "unconnected-(U7-IO22-Pad36)") (class "Default")
      (node (ref "U7") (pin "36") (pinfunction "IO22_36") (pintype "passive"))
    )
    (net (code "81") (name "unconnected-(U7-IO23-Pad37)") (class "Default")
      (node (ref "U7") (pin "37") (pinfunction "IO23_37") (pintype "passive"))
    )
    (net (code "82") (name "unconnected-(U7-IO25-Pad10)") (class "Default")
      (node (ref "U7") (pin "10") (pinfunction "IO25_10") (pintype "passive"))
    )
    (net (code "83") (name "unconnected-(U7-IO26-Pad11)") (class "Default")
      (node (ref "U7") (pin "11") (pinfunction "IO26_11") (pintype "passive"))
    )
    (net (code "84") (name "unconnected-(U7-IO27-Pad12)") (class "Default")
      (node (ref "U7") (pin "12") (pinfunction "IO27_12") (pintype "passive"))
    )
    (net (code "85") (name "unconnected-(U7-IO32-Pad8)") (class "Default")
      (node (ref "U7") (pin "8") (pinfunction "IO32_8") (pintype "passive"))
    )
    (net (code "86") (name "unconnected-(U7-IO33-Pad9)") (class "Default")
      (node (ref "U7") (pin "9") (pinfunction "IO33_9") (pintype "passive"))
    )
    (net (code "87") (name "unconnected-(U7-IO34-Pad6)") (class "Default")
      (node (ref "U7") (pin "6") (pinfunction "IO34_6") (pintype "passive"))
    )
    (net (code "88") (name "unconnected-(U7-IO35-Pad7)") (class "Default")
      (node (ref "U7") (pin "7") (pinfunction "IO35_7") (pintype "passive"))
    )
    (net (code "89") (name "unconnected-(U7-NC-Pad32)") (class "Default")
      (node (ref "U7") (pin "32") (pinfunction "NC_32") (pintype "passive"))
    )
    (net (code "90") (name "unconnected-(U7-SD0-Pad21)") (class "Default")
      (node (ref "U7") (pin "21") (pinfunction "SD0_21") (pintype "passive"))
    )
    (net (code "91") (name "unconnected-(U7-SD1-Pad22)") (class "Default")
      (node (ref "U7") (pin "22") (pinfunction "SD1_22") (pintype "passive"))
    )
    (net (code "92") (name "unconnected-(U7-SD2-Pad17)") (class "Default")
      (node (ref "U7") (pin "17") (pinfunction "SD2_17") (pintype "passive"))
    )
    (net (code "93") (name "unconnected-(U7-SD3-Pad18)") (class "Default")
      (node (ref "U7") (pin "18") (pinfunction "SD3_18") (pintype "passive"))
    )
    (net (code "94") (name "unconnected-(U7-SENSOR_VN-Pad5)") (class "Default")
      (node (ref "U7") (pin "5") (pinfunction "SENSOR_VN_5") (pintype "passive"))
    )
    (net (code "95") (name "unconnected-(U7-SENSOR_VP-Pad4)") (class "Default")
      (node (ref "U7") (pin "4") (pinfunction "SENSOR_VP_4") (pintype "passive"))
    )
  )
)
